# 4_-Ethernet_PHY.net
KiCad netlist of a schematic drawn in Altium Designer
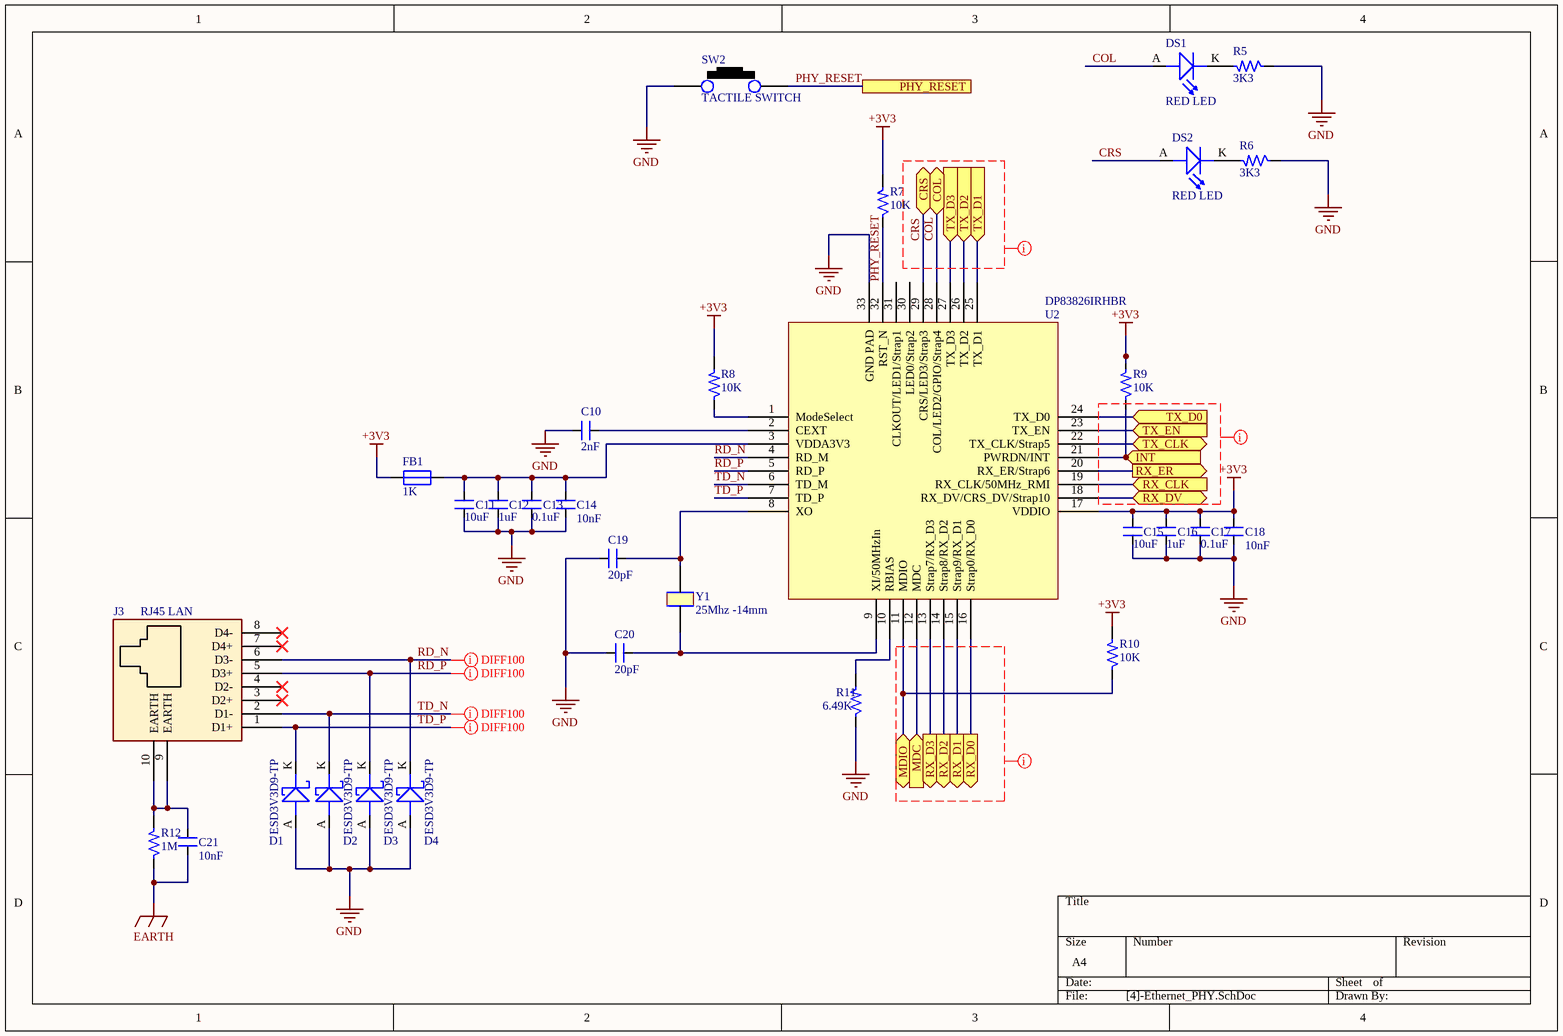
[diagram p0: [4]-Ethernet_PHY.SchDoc]

(export (version "E")
  (design (tool "Eeschema 10.0.6"))
  (components
    (comp (ref "C10")
      (value "2nF")
      (footprint "CAP_0805")
      (description "2000pF ±10% 50V Ceramic Capacitor X7R 0805 (2012 Metric)")
      (fields
        (field (name "MANUFACTURER") "Samsung Electro-Mechanics")
        (field (name "MANUFACTURER PART NUMBER") "CL21B202KBANNNC")
      )
      (libsource (lib "ESTEEMPCBLIB") (part "CAP_2nF-50V-10%-0805"))
    )
    (comp (ref "C11")
      (value "10uF")
      (footprint "CAP_1206")
      (description "10µF ±10% 50V Ceramic Capacitor X7R 1206 (3216 Metric)")
      (fields
        (field (name "MANUFACTURER") "KEMET")
        (field (name "MANUFACTURER PART NUMBER") "CL31B106KBHNNNE")
      )
      (libsource (lib "ESTEEMPCBLIB") (part "CAP_10uF-50V-10%-1206"))
    )
    (comp (ref "C12")
      (value "1uF")
      (footprint "CAP_0805")
      (description "1µF ±5% 50V Ceramic Capacitor X7R 0805 (2012 Metric)")
      (fields
        (field (name "MANUFACTURER") "Samsung")
        (field (name "MANUFACTURER PART NUMBER") "CC0805JKX7R9BB105")
      )
      (libsource (lib "ESTEEMPCBLIB") (part "CAP_1uF-50V-5%-0805"))
    )
    (comp (ref "C13")
      (value "0.1uF")
      (footprint "CAP_0805")
      (description "0.1µF ±10% 50V Ceramic Capacitor X7R 0805 (2012 Metric)")
      (fields
        (field (name "MANUFACTURER") "Samsung")
        (field (name "MANUFACTURER PART NUMBER") "CL21B104KBCNNNC")
      )
      (libsource (lib "ESTEEMPCBLIB") (part "CAP_0.1uF-50V-10%-0805"))
    )
    (comp (ref "C14")
      (value "10nF")
      (footprint "CAP_0805")
      (description "10000pF ±10% 50V Ceramic Capacitor X7R 0805 (2012 Metric)")
      (fields
        (field (name "MANUFACTURER") "Samsung")
        (field (name "MANUFACTURER PART NUMBER") "C0805C103K5RECAUTO")
      )
      (libsource (lib "ESTEEMPCBLIB") (part "CAP_10nF-50V-10%-0805"))
    )
    (comp (ref "C15")
      (value "10uF")
      (footprint "CAP_1206")
      (description "10µF ±10% 50V Ceramic Capacitor X7R 1206 (3216 Metric)")
      (fields
        (field (name "MANUFACTURER") "KEMET")
        (field (name "MANUFACTURER PART NUMBER") "CL31B106KBHNNNE")
      )
      (libsource (lib "ESTEEMPCBLIB") (part "CAP_10uF-50V-10%-1206"))
    )
    (comp (ref "C16")
      (value "1uF")
      (footprint "CAP_0805")
      (description "1µF ±5% 50V Ceramic Capacitor X7R 0805 (2012 Metric)")
      (fields
        (field (name "MANUFACTURER") "Samsung")
        (field (name "MANUFACTURER PART NUMBER") "CC0805JKX7R9BB105")
      )
      (libsource (lib "ESTEEMPCBLIB") (part "CAP_1uF-50V-5%-0805"))
    )
    (comp (ref "C17")
      (value "0.1uF")
      (footprint "CAP_0805")
      (description "0.1µF ±10% 50V Ceramic Capacitor X7R 0805 (2012 Metric)")
      (fields
        (field (name "MANUFACTURER") "Samsung")
        (field (name "MANUFACTURER PART NUMBER") "CL21B104KBCNNNC")
      )
      (libsource (lib "ESTEEMPCBLIB") (part "CAP_0.1uF-50V-10%-0805"))
    )
    (comp (ref "C18")
      (value "10nF")
      (footprint "CAP_0805")
      (description "10000pF ±10% 50V Ceramic Capacitor X7R 0805 (2012 Metric)")
      (fields
        (field (name "MANUFACTURER") "Samsung")
        (field (name "MANUFACTURER PART NUMBER") "C0805C103K5RECAUTO")
      )
      (libsource (lib "ESTEEMPCBLIB") (part "CAP_10nF-50V-10%-0805"))
    )
    (comp (ref "C19")
      (value "20pF")
      (footprint "CAP_0805")
      (description "±10% 50V Ceramic Capacitor C0G, NP0 0805 (2012 Metric)")
      (fields
        (field (name "MANUFACTURER") "AVX Corporation")
        (field (name "MANUFACTURER PART NUMBER") "08055A200KAT2A")
      )
      (libsource (lib "ESTEEMPCBLIB") (part "CAP_20pF-50V-10%-0805"))
    )
    (comp (ref "C20")
      (value "20pF")
      (footprint "CAP_0805")
      (description "±10% 50V Ceramic Capacitor C0G, NP0 0805 (2012 Metric)")
      (fields
        (field (name "MANUFACTURER") "AVX Corporation")
        (field (name "MANUFACTURER PART NUMBER") "08055A200KAT2A")
      )
      (libsource (lib "ESTEEMPCBLIB") (part "CAP_20pF-50V-10%-0805"))
    )
    (comp (ref "C21")
      (value "10nF")
      (footprint "CAP_P196_102X287_H332_RAD_TH")
      (description "10000pF ±10% 1000V (1kV) Ceramic Capacitor X7R Radial")
      (fields
        (field (name "MANUFACTURER") "Yageo")
        (field (name "MANUFACTURER PART NUMBER") "RDER73A103K2K1H03B")
      )
      (libsource (lib "ESTEEMPCBLIB") (part "CAP_10nF-1KV-10%-RAD-TH"))
    )
    (comp (ref "D1")
      (value "ESD3V3D9-TP")
      (footprint "DIO_SOD-923")
      (description "8.8V Clamp 5A (8/20µs) Ipp Tvs Diode Surface Mount SOD-923")
      (fields (field (name "MANUFACTURER") "Micro Commercial Co"))
      (libsource (lib "ESTEEMPCBLIB") (part "DIO-T_3.3V-8.8V-SOD923"))
    )
    (comp (ref "D2")
      (value "ESD3V3D9-TP")
      (footprint "DIO_SOD-923")
      (description "8.8V Clamp 5A (8/20µs) Ipp Tvs Diode Surface Mount SOD-923")
      (fields (field (name "MANUFACTURER") "Micro Commercial Co"))
      (libsource (lib "ESTEEMPCBLIB") (part "DIO-T_3.3V-8.8V-SOD923"))
    )
    (comp (ref "D3")
      (value "ESD3V3D9-TP")
      (footprint "DIO_SOD-923")
      (description "8.8V Clamp 5A (8/20µs) Ipp Tvs Diode Surface Mount SOD-923")
      (fields (field (name "MANUFACTURER") "Micro Commercial Co"))
      (libsource (lib "ESTEEMPCBLIB") (part "DIO-T_3.3V-8.8V-SOD923"))
    )
    (comp (ref "D4")
      (value "ESD3V3D9-TP")
      (footprint "DIO_SOD-923")
      (description "8.8V Clamp 5A (8/20µs) Ipp Tvs Diode Surface Mount SOD-923")
      (fields (field (name "MANUFACTURER") "Micro Commercial Co"))
      (libsource (lib "ESTEEMPCBLIB") (part "DIO-T_3.3V-8.8V-SOD923"))
    )
    (comp (ref "DS1")
      (value "RED LED")
      (footprint "LED_0805")
      (description "Red 631nm LED Indication - Discrete 2V 0805 (2012 Metric)")
      (fields
        (field (name "MANUFACTURER") "Vishay Lite-On")
        (field (name "MANUFACTURER PART NUMBER") "LTST-C171KRKT")
      )
      (libsource (lib "ESTEEMPCBLIB") (part "LED_RED-2V-20mA-0805"))
    )
    (comp (ref "DS2")
      (value "RED LED")
      (footprint "LED_0805")
      (description "Red 631nm LED Indication - Discrete 2V 0805 (2012 Metric)")
      (fields
        (field (name "MANUFACTURER") "Vishay Lite-On")
        (field (name "MANUFACTURER PART NUMBER") "LTST-C171KRKT")
      )
      (libsource (lib "ESTEEMPCBLIB") (part "LED_RED-2V-20mA-0805"))
    )
    (comp (ref "FB1")
      (value "1K")
      (footprint "IND_0805")
      (description "1 kOhms @ 100MHz 1 Power Line Ferrite Bead 0805 (2012 Metric) 1.6A")
      (fields
        (field (name "MANUFACTURER") "Laird")
        (field (name "MANUFACTURER PART NUMBER") "BLM21SP102SH1D")
      )
      (libsource (lib "ESTEEMPCBLIB") (part "FB_1K-100MHZ-1.6A-0805"))
    )
    (comp (ref "J3")
      (value "RJ45 LAN")
      (footprint "CON10_P106_RJ45_TH_ST")
      (description "8 Pins, 2 Row 2.54mm Pitch, right angle Connector, male")
      (fields
        (field (name "MANUFACTURER") "Assmann")
        (field (name "MANUFACTURER PART NUMBER") "A-2004-2-4-LPS-N-R")
      )
      (libsource (lib "ESTEEMPCBLIB") (part "CON-SKT-RJ_8C8P-RA-TH"))
    )
    (comp (ref "R5")
      (value "3K3")
      (footprint "RES_0603")
      (description "3.3 kOhms ±1% 0.1W, 1/10W Chip Resistor 0603 (1608 Metric) Automotive AEC-Q200 Thick Film")
      (fields (field (name "MANUFACTURER") "Wilson") (field (name "MANUFACTURER PART NUMBER") "WR06X3301FTL"))
      (libsource (lib "ESTEEMPCBLIB") (part "RES_3.3K-0.1W-1%-0603"))
    )
    (comp (ref "R6")
      (value "3K3")
      (footprint "RES_0603")
      (description "3.3 kOhms ±1% 0.1W, 1/10W Chip Resistor 0603 (1608 Metric) Automotive AEC-Q200 Thick Film")
      (fields (field (name "MANUFACTURER") "Wilson") (field (name "MANUFACTURER PART NUMBER") "WR06X3301FTL"))
      (libsource (lib "ESTEEMPCBLIB") (part "RES_3.3K-0.1W-1%-0603"))
    )
    (comp (ref "R7")
      (value "10K")
      (footprint "RES_0603")
      (description "10 kOhms ±1% 0.1W, 1/10W Chip Resistor 0603 (1608 Metric) Automotive AEC-Q200 Thick Film")
      (fields (field (name "MANUFACTURER") "Walsin") (field (name "MANUFACTURER PART NUMBER") "WR06X1002FTL"))
      (libsource (lib "ESTEEMPCBLIB") (part "RES_10K-0.1W-1%-0603"))
    )
    (comp (ref "R8")
      (value "10K")
      (footprint "RES_0603")
      (description "10 kOhms ±1% 0.1W, 1/10W Chip Resistor 0603 (1608 Metric) Automotive AEC-Q200 Thick Film")
      (fields (field (name "MANUFACTURER") "Walsin") (field (name "MANUFACTURER PART NUMBER") "WR06X1002FTL"))
      (libsource (lib "ESTEEMPCBLIB") (part "RES_10K-0.1W-1%-0603"))
    )
    (comp (ref "R9")
      (value "10K")
      (footprint "RES_0603")
      (description "10 kOhms ±1% 0.1W, 1/10W Chip Resistor 0603 (1608 Metric) Automotive AEC-Q200 Thick Film")
      (fields (field (name "MANUFACTURER") "Walsin") (field (name "MANUFACTURER PART NUMBER") "WR06X1002FTL"))
      (libsource (lib "ESTEEMPCBLIB") (part "RES_10K-0.1W-1%-0603"))
    )
    (comp (ref "R10")
      (value "10K")
      (footprint "RES_0603")
      (description "10 kOhms ±1% 0.1W, 1/10W Chip Resistor 0603 (1608 Metric) Automotive AEC-Q200 Thick Film")
      (fields (field (name "MANUFACTURER") "Walsin") (field (name "MANUFACTURER PART NUMBER") "WR06X1002FTL"))
      (libsource (lib "ESTEEMPCBLIB") (part "RES_10K-0.1W-1%-0603"))
    )
    (comp (ref "R11")
      (value "6.49K")
      (footprint "RES_0805")
      (description "6.49 kOhms ±1% 0.125W, 1/8W Chip Resistor 0805 (2012 Metric) Moisture Resistant Thick Film")
      (fields
        (field (name "MANUFACTURER") "Stackpole Electronics")
        (field (name "MANUFACTURER PART NUMBER") "RC0805FR-076K49L")
      )
      (libsource (lib "ESTEEMPCBLIB") (part "RES_6.49K-0.125W-1%-0805"))
    )
    (comp (ref "R12")
      (value "1M")
      (footprint "RES_1206")
      (fields (field (name "MANUFACTURER") "Walsin") (field (name "MANUFACTURER PART NUMBER") "WR12X1004FTL"))
      (libsource (lib "ESTEEMPCBLIB") (part "RES_1M-0.25W-1%-1206"))
    )
    (comp (ref "SW2")
      (value "TACTILE SWITCH")
      (footprint "SW_342_SMD")
      (description "Tactile Switch SPST-NO Top Actuated Surface Mount")
      (fields
        (field (name "MANUFACTURER") "ITT C&K")
        (field (name "MANUFACTURER PART NUMBER") "RS-282G05A3-SMRT")
      )
      (libsource (lib "ESTEEMPCBLIB") (part "SW1_RS-282G05A3-SMRT-SMD"))
    )
    (comp (ref "U2")
      (value "DP83826IRHBR")
      (footprint "VQFN32_19_218_23X9_SMD")
      (fields (field (name "MANUFACTURER") "Texas Instruments"))
      (libsource (lib "ESTEEMPCBLIB") (part "IC_DP83826IRHBR"))
    )
    (comp (ref "Y1")
      (value "25Mhz -14mm")
      (footprint "XTAL_314_240X47_SMD")
      (description "25MHz ±30ppm Crystal 20pF 30 Ohms HC-49/US")
      (fields
        (field (name "MANUFACTURER") "Abracon")
        (field (name "MANUFACTURER PART NUMBER") "FOXSDLF/250F-20")
      )
      (libsource (lib "ESTEEMPCBLIB") (part "XTAL_25Mhz-FOXSDLF/250F-20"))
    )
  )
  (nets
    (net (code "1") (name "+3V3") (class "Default")
      (node (ref "C15") (pin "2") (pinfunction "2_2") (pintype "passive"))
      (node (ref "C16") (pin "2") (pinfunction "2_2") (pintype "passive"))
      (node (ref "C17") (pin "2") (pinfunction "2_2") (pintype "passive"))
      (node (ref "C18") (pin "2") (pinfunction "2_2") (pintype "passive"))
      (node (ref "FB1") (pin "1") (pinfunction "1_1") (pintype "passive"))
      (node (ref "R10") (pin "2") (pinfunction "2_2") (pintype "passive"))
      (node (ref "R7") (pin "2") (pinfunction "2_2") (pintype "passive"))
      (node (ref "R8") (pin "2") (pinfunction "2_2") (pintype "passive"))
      (node (ref "R9") (pin "2") (pinfunction "2_2") (pintype "passive"))
      (node (ref "U2") (pin "17") (pinfunction "VDDIO_17") (pintype "passive"))
    )
    (net (code "2") (name "/COL") (class "Default")
      (node (ref "DS1") (pin "A") (pinfunction "ANODE_A") (pintype "passive"))
      (node (ref "U2") (pin "28") (pinfunction "COL/LED2/GPIO/Strap4_28") (pintype "passive"))
    )
    (net (code "3") (name "/CRS") (class "Default")
      (node (ref "DS2") (pin "A") (pinfunction "ANODE_A") (pintype "passive"))
      (node (ref "U2") (pin "29") (pinfunction "CRS/LED3/Strap3_29") (pintype "passive"))
    )
    (net (code "4") (name "/INT") (class "Default")
      (node (ref "R9") (pin "1") (pinfunction "1_1") (pintype "passive"))
      (node (ref "U2") (pin "21") (pinfunction "PWRDN/INT_21") (pintype "passive"))
    )
    (net (code "5") (name "/MDC") (class "Default")
      (node (ref "U2") (pin "12") (pinfunction "MDC_12") (pintype "passive"))
    )
    (net (code "6") (name "/MDIO") (class "Default")
      (node (ref "R10") (pin "1") (pinfunction "1_1") (pintype "passive"))
      (node (ref "U2") (pin "11") (pinfunction "MDIO_11") (pintype "passive"))
    )
    (net (code "7") (name "/PHY_RESET") (class "Default")
      (node (ref "R7") (pin "1") (pinfunction "1_1") (pintype "passive"))
      (node (ref "SW2") (pin "2") (pinfunction "2_2") (pintype "passive"))
      (node (ref "U2") (pin "32") (pinfunction "RST_N_32") (pintype "passive"))
    )
    (net (code "8") (name "/RD_N") (class "Default")
      (node (ref "D4") (pin "K") (pinfunction "K_K") (pintype "passive"))
      (node (ref "J3") (pin "6") (pinfunction "D3-_6") (pintype "passive"))
      (node (ref "U2") (pin "4") (pinfunction "RD_M_4") (pintype "passive"))
    )
    (net (code "9") (name "/RD_P") (class "Default")
      (node (ref "D3") (pin "K") (pinfunction "K_K") (pintype "passive"))
      (node (ref "J3") (pin "5") (pinfunction "D3+_5") (pintype "passive"))
      (node (ref "U2") (pin "5") (pinfunction "RD_P_5") (pintype "passive"))
    )
    (net (code "10") (name "/RX_CLK") (class "Default")
      (node (ref "U2") (pin "19") (pinfunction "RX_CLK/50MHz_RMI_19") (pintype "passive"))
    )
    (net (code "11") (name "/RX_D0") (class "Default")
      (node (ref "U2") (pin "16") (pinfunction "Strap0/RX_D0_16") (pintype "passive"))
    )
    (net (code "12") (name "/RX_D1") (class "Default")
      (node (ref "U2") (pin "15") (pinfunction "Strap9/RX_D1_15") (pintype "passive"))
    )
    (net (code "13") (name "/RX_D2") (class "Default")
      (node (ref "U2") (pin "14") (pinfunction "Strap8/RX_D2_14") (pintype "passive"))
    )
    (net (code "14") (name "/RX_D3") (class "Default")
      (node (ref "U2") (pin "13") (pinfunction "Strap7/RX_D3_13") (pintype "passive"))
    )
    (net (code "15") (name "/RX_DV") (class "Default")
      (node (ref "U2") (pin "18") (pinfunction "RX_DV/CRS_DV/Strap10_18") (pintype "passive"))
    )
    (net (code "16") (name "/RX_ER") (class "Default")
      (node (ref "U2") (pin "20") (pinfunction "RX_ER/Strap6_20") (pintype "passive"))
    )
    (net (code "17") (name "/TD_N") (class "Default")
      (node (ref "D2") (pin "K") (pinfunction "K_K") (pintype "passive"))
      (node (ref "J3") (pin "2") (pinfunction "D1-_2") (pintype "passive"))
      (node (ref "U2") (pin "6") (pinfunction "TD_M_6") (pintype "passive"))
    )
    (net (code "18") (name "/TD_P") (class "Default")
      (node (ref "D1") (pin "K") (pinfunction "K_K") (pintype "passive"))
      (node (ref "J3") (pin "1") (pinfunction "D1+_1") (pintype "passive"))
      (node (ref "U2") (pin "7") (pinfunction "TD_P_7") (pintype "passive"))
    )
    (net (code "19") (name "/TX_CLK") (class "Default")
      (node (ref "U2") (pin "22") (pinfunction "TX_CLK/Strap5_22") (pintype "passive"))
    )
    (net (code "20") (name "/TX_D0") (class "Default")
      (node (ref "U2") (pin "24") (pinfunction "TX_D0_24") (pintype "passive"))
    )
    (net (code "21") (name "/TX_D1") (class "Default")
      (node (ref "U2") (pin "25") (pinfunction "TX_D1_25") (pintype "passive"))
    )
    (net (code "22") (name "/TX_D2") (class "Default")
      (node (ref "U2") (pin "26") (pinfunction "TX_D2_26") (pintype "passive"))
    )
    (net (code "23") (name "/TX_D3") (class "Default")
      (node (ref "U2") (pin "27") (pinfunction "TX_D3_27") (pintype "passive"))
    )
    (net (code "24") (name "/TX_EN") (class "Default")
      (node (ref "U2") (pin "23") (pinfunction "TX_EN_23") (pintype "passive"))
    )
    (net (code "25") (name "EARTH") (class "Default")
      (node (ref "C21") (pin "1") (pinfunction "1_1") (pintype "passive"))
      (node (ref "R12") (pin "1") (pinfunction "1_1") (pintype "passive"))
    )
    (net (code "26") (name "GND") (class "Default")
      (node (ref "C10") (pin "1") (pinfunction "1_1") (pintype "passive"))
      (node (ref "C11") (pin "1") (pinfunction "1_1") (pintype "passive"))
      (node (ref "C12") (pin "1") (pinfunction "1_1") (pintype "passive"))
      (node (ref "C13") (pin "1") (pinfunction "1_1") (pintype "passive"))
      (node (ref "C14") (pin "1") (pinfunction "1_1") (pintype "passive"))
      (node (ref "C15") (pin "1") (pinfunction "1_1") (pintype "passive"))
      (node (ref "C16") (pin "1") (pinfunction "1_1") (pintype "passive"))
      (node (ref "C17") (pin "1") (pinfunction "1_1") (pintype "passive"))
      (node (ref "C18") (pin "1") (pinfunction "1_1") (pintype "passive"))
      (node (ref "C19") (pin "1") (pinfunction "1_1") (pintype "passive"))
      (node (ref "C20") (pin "1") (pinfunction "1_1") (pintype "passive"))
      (node (ref "D1") (pin "A") (pinfunction "A_A") (pintype "passive"))
      (node (ref "D2") (pin "A") (pinfunction "A_A") (pintype "passive"))
      (node (ref "D3") (pin "A") (pinfunction "A_A") (pintype "passive"))
      (node (ref "D4") (pin "A") (pinfunction "A_A") (pintype "passive"))
      (node (ref "R11") (pin "1") (pinfunction "1_1") (pintype "passive"))
      (node (ref "R5") (pin "1") (pinfunction "1_1") (pintype "passive"))
      (node (ref "R6") (pin "1") (pinfunction "1_1") (pintype "passive"))
      (node (ref "SW2") (pin "1") (pinfunction "1_1") (pintype "passive"))
      (node (ref "U2") (pin "33") (pinfunction "GND_PAD_33") (pintype "passive"))
    )
    (net (code "27") (name "Net-(C21-Pad2)") (class "Default")
      (node (ref "C21") (pin "2") (pinfunction "2_2") (pintype "passive"))
      (node (ref "J3") (pin "10") (pinfunction "EARTH_10") (pintype "passive"))
      (node (ref "J3") (pin "9") (pinfunction "EARTH_9") (pintype "passive"))
      (node (ref "R12") (pin "2") (pinfunction "2_2") (pintype "passive"))
    )
    (net (code "28") (name "Net-(DS1-CATHODE)") (class "Default")
      (node (ref "DS1") (pin "K") (pinfunction "CATHODE_K") (pintype "passive"))
      (node (ref "R5") (pin "2") (pinfunction "2_2") (pintype "passive"))
    )
    (net (code "29") (name "Net-(DS2-CATHODE)") (class "Default")
      (node (ref "DS2") (pin "K") (pinfunction "CATHODE_K") (pintype "passive"))
      (node (ref "R6") (pin "2") (pinfunction "2_2") (pintype "passive"))
    )
    (net (code "30") (name "Net-(U2-CEXT)") (class "Default")
      (node (ref "C10") (pin "2") (pinfunction "2_2") (pintype "passive"))
      (node (ref "U2") (pin "2") (pinfunction "CEXT_2") (pintype "passive"))
    )
    (net (code "31") (name "Net-(U2-ModeSelect)") (class "Default")
      (node (ref "R8") (pin "1") (pinfunction "1_1") (pintype "passive"))
      (node (ref "U2") (pin "1") (pinfunction "ModeSelect_1") (pintype "passive"))
    )
    (net (code "32") (name "Net-(U2-RBIAS)") (class "Default")
      (node (ref "R11") (pin "2") (pinfunction "2_2") (pintype "passive"))
      (node (ref "U2") (pin "10") (pinfunction "RBIAS_10") (pintype "passive"))
    )
    (net (code "33") (name "Net-(U2-VDDA3V3)") (class "Default")
      (node (ref "C11") (pin "2") (pinfunction "2_2") (pintype "passive"))
      (node (ref "C12") (pin "2") (pinfunction "2_2") (pintype "passive"))
      (node (ref "C13") (pin "2") (pinfunction "2_2") (pintype "passive"))
      (node (ref "C14") (pin "2") (pinfunction "2_2") (pintype "passive"))
      (node (ref "FB1") (pin "2") (pinfunction "2_2") (pintype "passive"))
      (node (ref "U2") (pin "3") (pinfunction "VDDA3V3_3") (pintype "passive"))
    )
    (net (code "34") (name "Net-(U2-XI{slash}50MHzIn)") (class "Default")
      (node (ref "C20") (pin "2") (pinfunction "2_2") (pintype "passive"))
      (node (ref "U2") (pin "9") (pinfunction "XI/50MHzIn_9") (pintype "passive"))
      (node (ref "Y1") (pin "1") (pinfunction "1_1") (pintype "passive"))
    )
    (net (code "35") (name "Net-(U2-XO)") (class "Default")
      (node (ref "C19") (pin "2") (pinfunction "2_2") (pintype "passive"))
      (node (ref "U2") (pin "8") (pinfunction "XO_8") (pintype "passive"))
      (node (ref "Y1") (pin "2") (pinfunction "2_2") (pintype "passive"))
    )
    (net (code "36") (name "unconnected-(J3-D2+-Pad3)") (class "Default")
      (node (ref "J3") (pin "3") (pinfunction "D2+_3") (pintype "passive+no_connect"))
    )
    (net (code "37") (name "unconnected-(J3-D2--Pad4)") (class "Default")
      (node (ref "J3") (pin "4") (pinfunction "D2-_4") (pintype "passive+no_connect"))
    )
    (net (code "38") (name "unconnected-(J3-D4+-Pad7)") (class "Default")
      (node (ref "J3") (pin "7") (pinfunction "D4+_7") (pintype "passive+no_connect"))
    )
    (net (code "39") (name "unconnected-(J3-D4--Pad8)") (class "Default")
      (node (ref "J3") (pin "8") (pinfunction "D4-_8") (pintype "passive+no_connect"))
    )
    (net (code "40") (name "unconnected-(U2-CLKOUT{slash}LED1{slash}Strap1-Pad31)") (class "Default")
      (node (ref "U2") (pin "31") (pinfunction "CLKOUT/LED1/Strap1_31") (pintype "passive"))
    )
    (net (code "41") (name "unconnected-(U2-LED0{slash}Strap2-Pad30)") (class "Default")
      (node (ref "U2") (pin "30") (pinfunction "LED0/Strap2_30") (pintype "passive"))
    )
  )
)
